# ADC_Reference_Voltage.net
KiCad netlist of a schematic drawn in Altium Designer
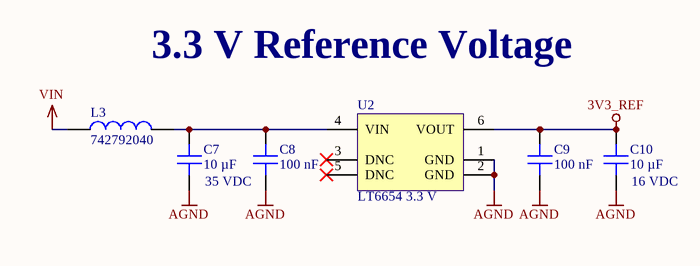
[diagram p0: ADC_Reference_Voltage.SchDoc]

(export (version "E")
  (design (tool "Eeschema 10.0.6"))
  (components
    (comp (ref "C7")
      (value "10 µF")
      (footprint "CAPC_0805_L")
      (description "Capacitor 0805, 35 VDC, 10 µF, X5R")
      (fields
        (field (name "MANUFACTURER PART NUMBER") "GRM21BR6YA106KE43L")
        (field (name "MANUFACTURER") "Murata Electronics")
        (field (name "VOLTAGE RATING") "35 VDC")
        (field (name "CREATED FROM") "AGeiger")
      )
      (libsource (lib "user") (part "Capacitor"))
    )
    (comp (ref "C8")
      (value "100 nF")
      (footprint "C_0603")
      (description "Capacitor 0603, 50 VDC, 100 nF, X7R")
      (fields
        (field (name "MANUFACTURER PART NUMBER") "CC0603KRX7R9BB104")
        (field (name "MANUFACTURER") "YAGEO")
        (field (name "CREATED FROM") "AGeiger")
      )
      (libsource (lib "user") (part "Capacitor"))
    )
    (comp (ref "C9")
      (value "100 nF")
      (footprint "C_0603")
      (description "Capacitor 0603, 50 VDC, 100 nF, X7R")
      (fields
        (field (name "MANUFACTURER PART NUMBER") "CC0603KRX7R9BB104")
        (field (name "MANUFACTURER") "YAGEO")
        (field (name "CREATED FROM") "AGeiger")
      )
      (libsource (lib "user") (part "Capacitor"))
    )
    (comp (ref "C10")
      (value "10 µF")
      (footprint "C_0603")
      (description "Capacitor 0603, 16 VDC, 10 µF, X5R")
      (fields
        (field (name "MANUFACTURER PART NUMBER") "CL10A106MO8NQNC")
        (field (name "MANUFACTURER") "Samsung Electro-Mechanics")
        (field (name "VOLTAGE RATING") "16 VDC")
        (field (name "CREATED FROM") "AGeiger")
      )
      (libsource (lib "user") (part "Capacitor"))
    )
    (comp (ref "L3")
      (value "742792040")
      (footprint "WE-CBF_0805_High Current")
      (description "Inductance, 0805, 100 MHz, 600 Ohm, 2 A")
      (fields
        (field (name "MANUFACTURER") "Wurth Elektronik")
        (field (name "LCSC PART NUMBER") "C2661857")
        (field (name "CREATED FROM") "AGeiger")
      )
      (libsource (lib "user") (part "WE-CBF"))
    )
    (comp (ref "U2")
      (value "LT6654 3.3 V")
      (footprint "SOT95P280X100-6N")
      (description "Voltage Reference, 3.3V, ±0.05%, ±10mA")
      (fields
        (field (name "MANUFACTURER PART NUMBER") "LT6654AIS6-3.3#TRMPBF")
        (field (name "MANUFACTURER") "Analog Devices")
        (field (name "CREATED FROM") "AGeiger")
      )
      (libsource (lib "user") (part "LT6654xxS"))
    )
  )
  (nets
    (net (code "1") (name "3V3_REF") (class "Default")
      (node (ref "C10") (pin "2") (pinfunction "2_2") (pintype "passive"))
      (node (ref "C9") (pin "2") (pinfunction "2_2") (pintype "passive"))
      (node (ref "U2") (pin "6") (pinfunction "VOUT_6") (pintype "power_in"))
    )
    (net (code "2") (name "AGND") (class "Default")
      (node (ref "C10") (pin "1") (pinfunction "1_1") (pintype "passive"))
      (node (ref "C7") (pin "1") (pinfunction "1_1") (pintype "passive"))
      (node (ref "C8") (pin "1") (pinfunction "1_1") (pintype "passive"))
      (node (ref "C9") (pin "1") (pinfunction "1_1") (pintype "passive"))
      (node (ref "U2") (pin "1") (pinfunction "GND_1") (pintype "power_in"))
      (node (ref "U2") (pin "2") (pinfunction "GND_2") (pintype "power_in"))
    )
    (net (code "3") (name "Net-(U2-VIN)") (class "Default")
      (node (ref "C7") (pin "2") (pinfunction "2_2") (pintype "passive"))
      (node (ref "C8") (pin "2") (pinfunction "2_2") (pintype "passive"))
      (node (ref "L3") (pin "2") (pinfunction "2_2") (pintype "passive"))
      (node (ref "U2") (pin "4") (pinfunction "VIN_4") (pintype "power_in"))
    )
    (net (code "4") (name "VIN") (class "Default")
      (node (ref "L3") (pin "1") (pinfunction "1_1") (pintype "passive"))
    )
    (net (code "5") (name "unconnected-(U2-DNC-Pad3)") (class "Default")
      (node (ref "U2") (pin "3") (pinfunction "DNC_3") (pintype "passive+no_connect"))
    )
    (net (code "6") (name "unconnected-(U2-DNC-Pad5)") (class "Default")
      (node (ref "U2") (pin "5") (pinfunction "DNC_5") (pintype "passive+no_connect"))
    )
  )
)
